# Sheet1.net
KiCad netlist of a schematic drawn in Altium Designer
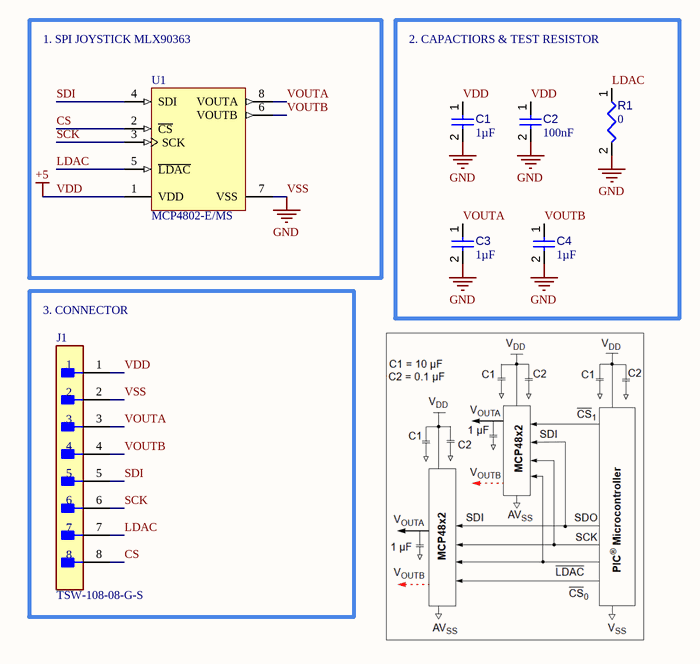
[diagram p0: Sheet1.SchDoc]

(export (version "E")
  (design (tool "Eeschema 10.0.6"))
  (components
    (comp (ref "C1")
      (value "1µF")
      (footprint "CAPC0402(1005)60_L")
      (description "Chip Capacitor, 1µF +/-20%, 10V, 0402, Thickness 0.6 mm")
      (fields (field (name "TOLERANCE") "10%") (field (name "Comment") "Capacitor 1µF +/-20% 10V 0402"))
      (libsource (lib "SUBC") (part "CAP-NP-2"))
    )
    (comp (ref "C2")
      (value "100nF")
      (footprint "CAPC0402(1005)60_L")
      (description "Chip Capacitor, 100nF +/-20%, 25V, 0402, Thickness 0.6 mm")
      (fields (field (name "TOLERANCE") "10%") (field (name "Comment") "Capacitor 100nF +/-20% 25V 0402"))
      (libsource (lib "SUBC") (part "CAP-NP-2"))
    )
    (comp (ref "C3")
      (value "1µF")
      (footprint "CAPC0402(1005)60_L")
      (description "Chip Capacitor, 1µF +/-20%, 10V, 0402, Thickness 0.6 mm")
      (fields (field (name "TOLERANCE") "10%") (field (name "Comment") "Capacitor 1µF +/-20% 10V 0402"))
      (libsource (lib "SUBC") (part "CAP-NP-2"))
    )
    (comp (ref "C4")
      (value "1µF")
      (footprint "CAPC0402(1005)60_L")
      (description "Chip Capacitor, 1µF +/-20%, 10V, 0402, Thickness 0.6 mm")
      (fields (field (name "TOLERANCE") "10%") (field (name "Comment") "Capacitor 1µF +/-20% 10V 0402"))
      (libsource (lib "SUBC") (part "CAP-NP-2"))
    )
    (comp (ref "J1")
      (value "TSW-108-08-G-S")
      (footprint "FP-TSW-108-08-G-S-MFG")
      (description "TSW - Samtec 2.54mm Pin Header 13.46mm Overall Pin Length 5.08mm Tail (08) (mcv)(TO22)")
      (libsource (lib "SUBC") (part "99ec2b232beb5d2356d4d77f6a047f0"))
    )
    (comp (ref "R1")
      (value "0")
      (footprint "RESC0402(1005)_L")
      (description "Jumper 0402 (1005 Metric)")
      (fields (field (name "Comment") "0R2J"))
      (libsource (lib "SUBC") (part "0R2J"))
    )
    (comp (ref "U1")
      (value "MCP4802-E/MS")
      (footprint "MSOP-MS8_N")
      (description "DAC 2-CH Resistor-String 8-bit Automotive 8-Pin MSOP Tube")
      (libsource (lib "SUBC") (part "CON-DAC-MCP4822-8"))
    )
  )
  (nets
    (net (code "1") (name "+5") (class "Default")
      (node (ref "C1") (pin "1") (pinfunction "1_1") (pintype "passive"))
      (node (ref "C2") (pin "1") (pinfunction "1_1") (pintype "passive"))
      (node (ref "J1") (pin "1") (pinfunction "1_1") (pintype "passive"))
      (node (ref "U1") (pin "1") (pinfunction "VDD_1") (pintype "power_in"))
    )
    (net (code "2") (name "/CS") (class "Default")
      (node (ref "J1") (pin "8") (pinfunction "8_8") (pintype "passive"))
      (node (ref "U1") (pin "2") (pinfunction "~{CS}_2") (pintype "input"))
    )
    (net (code "3") (name "/LDAC") (class "Default")
      (node (ref "J1") (pin "7") (pinfunction "7_7") (pintype "passive"))
      (node (ref "R1") (pin "1") (pinfunction "1_1") (pintype "passive"))
      (node (ref "U1") (pin "5") (pinfunction "~{LDAC}_5") (pintype "input"))
    )
    (net (code "4") (name "/SCK") (class "Default")
      (node (ref "J1") (pin "6") (pinfunction "6_6") (pintype "passive"))
      (node (ref "U1") (pin "3") (pinfunction "SCK_3") (pintype "input"))
    )
    (net (code "5") (name "/SDI") (class "Default")
      (node (ref "J1") (pin "5") (pinfunction "5_5") (pintype "passive"))
      (node (ref "U1") (pin "4") (pinfunction "SDI_4") (pintype "input"))
    )
    (net (code "6") (name "/VOUTA") (class "Default")
      (node (ref "C3") (pin "1") (pinfunction "1_1") (pintype "passive"))
      (node (ref "J1") (pin "3") (pinfunction "3_3") (pintype "passive"))
      (node (ref "U1") (pin "8") (pinfunction "VOUTA_8") (pintype "output"))
    )
    (net (code "7") (name "/VOUTB") (class "Default")
      (node (ref "C4") (pin "1") (pinfunction "1_1") (pintype "passive"))
      (node (ref "J1") (pin "4") (pinfunction "4_4") (pintype "passive"))
      (node (ref "U1") (pin "6") (pinfunction "VOUTB_6") (pintype "output"))
    )
    (net (code "8") (name "GND") (class "Default")
      (node (ref "C1") (pin "2") (pinfunction "2_2") (pintype "passive"))
      (node (ref "C2") (pin "2") (pinfunction "2_2") (pintype "passive"))
      (node (ref "C3") (pin "2") (pinfunction "2_2") (pintype "passive"))
      (node (ref "C4") (pin "2") (pinfunction "2_2") (pintype "passive"))
      (node (ref "J1") (pin "2") (pinfunction "2_2") (pintype "passive"))
      (node (ref "R1") (pin "2") (pinfunction "2_2") (pintype "passive"))
      (node (ref "U1") (pin "7") (pinfunction "VSS_7") (pintype "power_in"))
    )
  )
)
